# Charge_Interface.net
KiCad netlist of a schematic drawn in Altium Designer
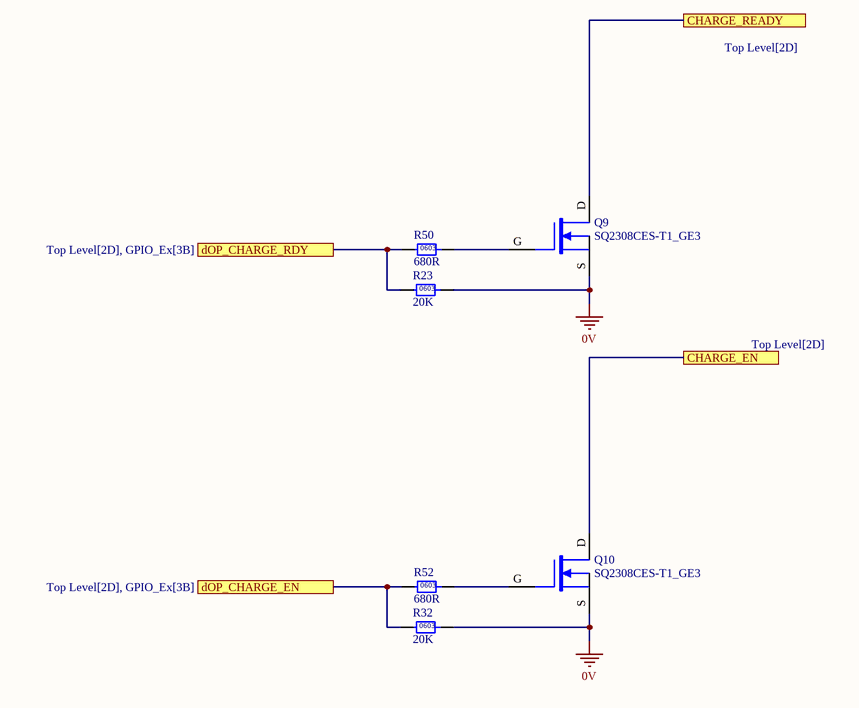
[diagram p0: Charge Interface.SchDoc]

(export (version "E")
  (design (tool "Eeschema 10.0.6"))
  (components
    (comp (ref "Q9")
      (value "SQ2308CES-T1_GE3")
      (footprint "VSHY SOT-23-3")
      (description "MOSFET N-CH 60V 2.3A SOT23")
      (fields
        (field (name "MANUFACTURER") "Vishay Siliconix")
        (field (name "DIGIKEY PART NUMBER") "SQ2308CES-T1_GE3CT-ND")
        (field (name "PUBLISHER") "Altium Limited")
      )
      (libsource (lib "ts_standard_library") (part "MOSFET-N"))
    )
    (comp (ref "Q10")
      (value "SQ2308CES-T1_GE3")
      (footprint "VSHY SOT-23-3")
      (description "MOSFET N-CH 60V 2.3A SOT23")
      (fields
        (field (name "MANUFACTURER") "Vishay Siliconix")
        (field (name "DIGIKEY PART NUMBER") "SQ2308CES-T1_GE3CT-ND")
        (field (name "PUBLISHER") "Altium Limited")
      )
      (libsource (lib "ts_standard_library") (part "MOSFET-N"))
    )
    (comp (ref "R23")
      (value "20K")
      (footprint "0603")
      (fields
        (field (name "PART NUMBER") "RC0603FR-0720KL")
        (field (name "MANUFACTURER") "YAGEO")
        (field (name "TOLERANCE") "0.01")
      )
      (libsource (lib "ts_standard_library") (part "Resistor 0603"))
    )
    (comp (ref "R32")
      (value "20K")
      (footprint "0603")
      (fields
        (field (name "PART NUMBER") "RC0603FR-0720KL")
        (field (name "MANUFACTURER") "YAGEO")
        (field (name "TOLERANCE") "0.01")
      )
      (libsource (lib "ts_standard_library") (part "Resistor 0603"))
    )
    (comp (ref "R50")
      (value "680R")
      (footprint "0603")
      (fields
        (field (name "PART NUMBER") "RC0603JR-13680RL")
        (field (name "MANUFACTURER") "YAGEO")
        (field (name "TOLERANCE") "0.01")
      )
      (libsource (lib "ts_standard_library") (part "Resistor 0603"))
    )
    (comp (ref "R52")
      (value "680R")
      (footprint "0603")
      (fields
        (field (name "PART NUMBER") "RC0603JR-13680RL")
        (field (name "MANUFACTURER") "YAGEO")
        (field (name "TOLERANCE") "0.01")
      )
      (libsource (lib "ts_standard_library") (part "Resistor 0603"))
    )
  )
  (nets
    (net (code "1") (name "/CHARGE_EN") (class "Default")
      (node (ref "Q10") (pin "D") (pinfunction "D_D") (pintype "passive"))
    )
    (net (code "2") (name "/CHARGE_READY") (class "Default")
      (node (ref "Q9") (pin "D") (pinfunction "D_D") (pintype "passive"))
    )
    (net (code "3") (name "/dOP_CHARGE_EN") (class "Default")
      (node (ref "R32") (pin "1") (pinfunction "1_1") (pintype "passive"))
      (node (ref "R52") (pin "1") (pinfunction "1_1") (pintype "passive"))
    )
    (net (code "4") (name "/dOP_CHARGE_RDY") (class "Default")
      (node (ref "R23") (pin "1") (pinfunction "1_1") (pintype "passive"))
      (node (ref "R50") (pin "1") (pinfunction "1_1") (pintype "passive"))
    )
    (net (code "5") (name "0V") (class "Default")
      (node (ref "Q10") (pin "S") (pinfunction "S_S") (pintype "passive"))
      (node (ref "Q9") (pin "S") (pinfunction "S_S") (pintype "passive"))
      (node (ref "R23") (pin "2") (pinfunction "2_2") (pintype "passive"))
      (node (ref "R32") (pin "2") (pinfunction "2_2") (pintype "passive"))
    )
    (net (code "6") (name "Net-(Q9-PadG)") (class "Default")
      (node (ref "Q9") (pin "G") (pinfunction "G_G") (pintype "passive"))
      (node (ref "R50") (pin "2") (pinfunction "2_2") (pintype "passive"))
    )
    (net (code "7") (name "Net-(Q10-PadG)") (class "Default")
      (node (ref "Q10") (pin "G") (pinfunction "G_G") (pintype "passive"))
      (node (ref "R52") (pin "2") (pinfunction "2_2") (pintype "passive"))
    )
  )
)
